# dual_vca_main.net
KiCad netlist of a schematic drawn in EAGLE
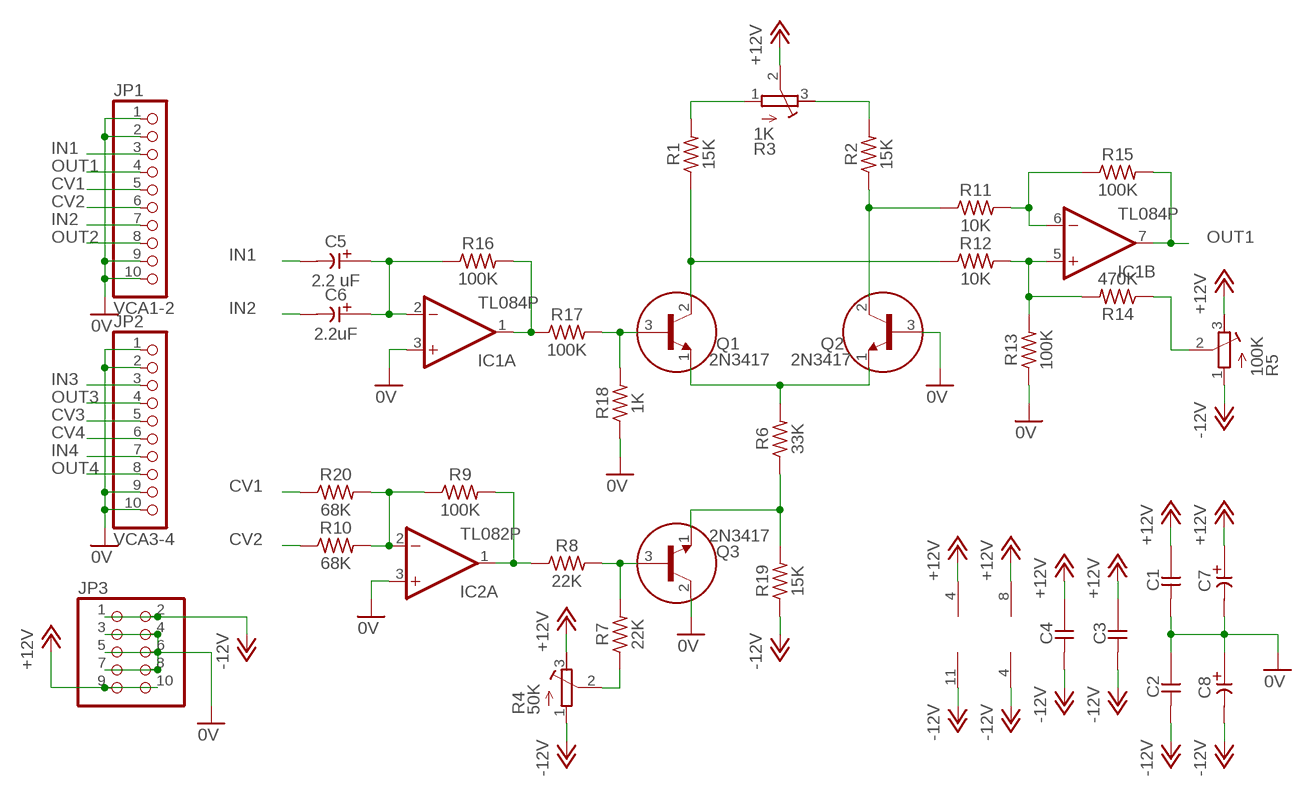
[diagram p0: schematic, sheet 1]

(export (version "E")
  (design (tool "Eeschema 10.0.6"))
  (components
    (comp (ref "C1")
      (value "CC-US025-024X044")
      (footprint "eagle-import:C025-024X044")
      (libsource (lib "eagle-import") (part "CC-US025-024X044"))
    )
    (comp (ref "C2")
      (value "CC-US025-024X044")
      (footprint "eagle-import:C025-024X044")
      (libsource (lib "eagle-import") (part "CC-US025-024X044"))
    )
    (comp (ref "C3")
      (value "CC-US025-024X044")
      (footprint "eagle-import:C025-024X044")
      (libsource (lib "eagle-import") (part "CC-US025-024X044"))
    )
    (comp (ref "C4")
      (value "CC-US025-024X044")
      (footprint "eagle-import:C025-024X044")
      (libsource (lib "eagle-import") (part "CC-US025-024X044"))
    )
    (comp (ref "C5")
      (value "2.2 uF")
      (footprint "eagle-import:E2-5")
      (libsource (lib "eagle-import") (part "CE-USE2-5"))
    )
    (comp (ref "C6")
      (value "2.2uF")
      (footprint "eagle-import:E2-5")
      (libsource (lib "eagle-import") (part "CE-USE2-5"))
    )
    (comp (ref "C7")
      (value "CE-USE2-5")
      (footprint "eagle-import:E2-5")
      (libsource (lib "eagle-import") (part "CE-USE2-5"))
    )
    (comp (ref "C8")
      (value "CE-USE2-5")
      (footprint "eagle-import:E2-5")
      (libsource (lib "eagle-import") (part "CE-USE2-5"))
    )
    (comp (ref "IC1")
      (value "TL084P")
      (footprint "eagle-import:DIL14")
      (libsource (lib "eagle-import") (part "TL084P"))
    )
    (comp (ref "IC2")
      (value "TL082P")
      (footprint "eagle-import:DIL08")
      (libsource (lib "eagle-import") (part "TL082P"))
    )
    (comp (ref "JP1")
      (value "VCA1-2")
      (footprint "eagle-import:1X10")
      (libsource (lib "eagle-import") (part "PINHD-1X10"))
    )
    (comp (ref "JP2")
      (value "VCA3-4")
      (footprint "eagle-import:1X10")
      (libsource (lib "eagle-import") (part "PINHD-1X10"))
    )
    (comp (ref "JP3")
      (value "PINHD-2X5")
      (footprint "eagle-import:2X05")
      (libsource (lib "eagle-import") (part "PINHD-2X5"))
    )
    (comp (ref "Q1")
      (value "2N3417")
      (footprint "eagle-import:TO92")
      (libsource (lib "eagle-import") (part "2N3417"))
    )
    (comp (ref "Q2")
      (value "2N3417")
      (footprint "eagle-import:TO92")
      (libsource (lib "eagle-import") (part "2N3417"))
    )
    (comp (ref "Q3")
      (value "2N3417")
      (footprint "eagle-import:TO92")
      (libsource (lib "eagle-import") (part "2N3417"))
    )
    (comp (ref "R1")
      (value "15K")
      (footprint "eagle-import:0207_7")
      (libsource (lib "eagle-import") (part "R"))
    )
    (comp (ref "R2")
      (value "15K")
      (footprint "eagle-import:0207_7")
      (libsource (lib "eagle-import") (part "R"))
    )
    (comp (ref "R3")
      (value "1K")
      (footprint "eagle-import:RTRIM3339P")
      (libsource (lib "eagle-import") (part "R-TRIMM3339P"))
    )
    (comp (ref "R4")
      (value "50K")
      (footprint "eagle-import:RTRIM3339P")
      (libsource (lib "eagle-import") (part "R-TRIMM3339P"))
    )
    (comp (ref "R5")
      (value "100K")
      (footprint "eagle-import:RTRIM3339P")
      (libsource (lib "eagle-import") (part "R-TRIMM3339P"))
    )
    (comp (ref "R6")
      (value "33K")
      (footprint "eagle-import:0207_7")
      (libsource (lib "eagle-import") (part "R"))
    )
    (comp (ref "R7")
      (value "22K")
      (footprint "eagle-import:0207_7")
      (libsource (lib "eagle-import") (part "R"))
    )
    (comp (ref "R8")
      (value "22K")
      (footprint "eagle-import:0207_7")
      (libsource (lib "eagle-import") (part "R"))
    )
    (comp (ref "R9")
      (value "100K")
      (footprint "eagle-import:0207_7")
      (libsource (lib "eagle-import") (part "R"))
    )
    (comp (ref "R10")
      (value "68K")
      (footprint "eagle-import:0207_7")
      (libsource (lib "eagle-import") (part "R"))
    )
    (comp (ref "R11")
      (value "10K")
      (footprint "eagle-import:0207_7")
      (libsource (lib "eagle-import") (part "R"))
    )
    (comp (ref "R12")
      (value "10K")
      (footprint "eagle-import:0207_7")
      (libsource (lib "eagle-import") (part "R"))
    )
    (comp (ref "R13")
      (value "100K")
      (footprint "eagle-import:0207_7")
      (libsource (lib "eagle-import") (part "R"))
    )
    (comp (ref "R14")
      (value "470K")
      (footprint "eagle-import:0207_7")
      (libsource (lib "eagle-import") (part "R"))
    )
    (comp (ref "R15")
      (value "100K")
      (footprint "eagle-import:0207_7")
      (libsource (lib "eagle-import") (part "R"))
    )
    (comp (ref "R16")
      (value "100K")
      (footprint "eagle-import:0207_7")
      (libsource (lib "eagle-import") (part "R"))
    )
    (comp (ref "R17")
      (value "100K")
      (footprint "eagle-import:0207_7")
      (libsource (lib "eagle-import") (part "R"))
    )
    (comp (ref "R18")
      (value "1K")
      (footprint "eagle-import:0207_7")
      (libsource (lib "eagle-import") (part "R"))
    )
    (comp (ref "R19")
      (value "15K")
      (footprint "eagle-import:0207_7")
      (libsource (lib "eagle-import") (part "R"))
    )
    (comp (ref "R20")
      (value "68K")
      (footprint "eagle-import:0207_7")
      (libsource (lib "eagle-import") (part "R"))
    )
  )
  (nets
    (net (code "1") (name "+12V") (class "Default")
      (node (ref "C1") (pin "1") (pinfunction "1_1") (pintype "passive"))
      (node (ref "C3") (pin "1") (pinfunction "1_1") (pintype "passive"))
      (node (ref "C4") (pin "1") (pinfunction "1_1") (pintype "passive"))
      (node (ref "C7") (pin "+") (pinfunction "+_+") (pintype "passive"))
      (node (ref "IC1") (pin "4") (pinfunction "V+_4") (pintype "power_in"))
      (node (ref "IC2") (pin "8") (pinfunction "V+_8") (pintype "power_in"))
      (node (ref "JP3") (pin "10") (pinfunction "10_10") (pintype "passive"))
      (node (ref "JP3") (pin "9") (pinfunction "9_9") (pintype "passive"))
      (node (ref "R3") (pin "2") (pinfunction "S_2") (pintype "passive"))
      (node (ref "R4") (pin "3") (pinfunction "E_3") (pintype "passive"))
      (node (ref "R5") (pin "3") (pinfunction "E_3") (pintype "passive"))
    )
    (net (code "2") (name "-12V") (class "Default")
      (node (ref "C2") (pin "2") (pinfunction "2_2") (pintype "passive"))
      (node (ref "C3") (pin "2") (pinfunction "2_2") (pintype "passive"))
      (node (ref "C4") (pin "2") (pinfunction "2_2") (pintype "passive"))
      (node (ref "C8") (pin "-") (pinfunction "-_-") (pintype "passive"))
      (node (ref "IC1") (pin "11") (pinfunction "V-_11") (pintype "power_in"))
      (node (ref "IC2") (pin "4") (pinfunction "V-_4") (pintype "power_in"))
      (node (ref "JP3") (pin "1") (pinfunction "1_1") (pintype "passive"))
      (node (ref "JP3") (pin "2") (pinfunction "2_2") (pintype "passive"))
      (node (ref "R19") (pin "1") (pinfunction "1_1") (pintype "passive"))
      (node (ref "R4") (pin "1") (pinfunction "A_1") (pintype "passive"))
      (node (ref "R5") (pin "1") (pinfunction "A_1") (pintype "passive"))
    )
    (net (code "3") (name "/CV1") (class "Default")
      (node (ref "JP1") (pin "5") (pinfunction "5_5") (pintype "passive"))
      (node (ref "R20") (pin "1") (pinfunction "1_1") (pintype "passive"))
    )
    (net (code "4") (name "/CV2") (class "Default")
      (node (ref "JP1") (pin "6") (pinfunction "6_6") (pintype "passive"))
      (node (ref "R10") (pin "1") (pinfunction "1_1") (pintype "passive"))
    )
    (net (code "5") (name "/CV3") (class "Default")
      (node (ref "JP2") (pin "5") (pinfunction "5_5") (pintype "passive"))
    )
    (net (code "6") (name "/CV4") (class "Default")
      (node (ref "JP2") (pin "6") (pinfunction "6_6") (pintype "passive"))
    )
    (net (code "7") (name "/IN1") (class "Default")
      (node (ref "C5") (pin "-") (pinfunction "-_-") (pintype "passive"))
      (node (ref "JP1") (pin "3") (pinfunction "3_3") (pintype "passive"))
    )
    (net (code "8") (name "/IN2") (class "Default")
      (node (ref "C6") (pin "-") (pinfunction "-_-") (pintype "passive"))
      (node (ref "JP1") (pin "7") (pinfunction "7_7") (pintype "passive"))
    )
    (net (code "9") (name "/IN3") (class "Default")
      (node (ref "JP2") (pin "3") (pinfunction "3_3") (pintype "passive"))
    )
    (net (code "10") (name "/IN4") (class "Default")
      (node (ref "JP2") (pin "7") (pinfunction "7_7") (pintype "passive"))
    )
    (net (code "11") (name "/OUT1") (class "Default")
      (node (ref "IC1") (pin "7") (pinfunction "OUT_7") (pintype "output"))
      (node (ref "JP1") (pin "4") (pinfunction "4_4") (pintype "passive"))
      (node (ref "R15") (pin "2") (pinfunction "2_2") (pintype "passive"))
    )
    (net (code "12") (name "/OUT2") (class "Default")
      (node (ref "JP1") (pin "8") (pinfunction "8_8") (pintype "passive"))
    )
    (net (code "13") (name "/OUT3") (class "Default")
      (node (ref "JP2") (pin "4") (pinfunction "4_4") (pintype "passive"))
    )
    (net (code "14") (name "/OUT4") (class "Default")
      (node (ref "JP2") (pin "8") (pinfunction "8_8") (pintype "passive"))
    )
    (net (code "15") (name "0V") (class "Default")
      (node (ref "C1") (pin "2") (pinfunction "2_2") (pintype "passive"))
      (node (ref "C2") (pin "1") (pinfunction "1_1") (pintype "passive"))
      (node (ref "C7") (pin "-") (pinfunction "-_-") (pintype "passive"))
      (node (ref "C8") (pin "+") (pinfunction "+_+") (pintype "passive"))
      (node (ref "IC1") (pin "3") (pinfunction "+IN_3") (pintype "input"))
      (node (ref "IC2") (pin "3") (pinfunction "+IN_3") (pintype "input"))
      (node (ref "JP1") (pin "1") (pinfunction "1_1") (pintype "passive"))
      (node (ref "JP1") (pin "10") (pinfunction "10_10") (pintype "passive"))
      (node (ref "JP1") (pin "2") (pinfunction "2_2") (pintype "passive"))
      (node (ref "JP1") (pin "9") (pinfunction "9_9") (pintype "passive"))
      (node (ref "JP2") (pin "1") (pinfunction "1_1") (pintype "passive"))
      (node (ref "JP2") (pin "10") (pinfunction "10_10") (pintype "passive"))
      (node (ref "JP2") (pin "2") (pinfunction "2_2") (pintype "passive"))
      (node (ref "JP2") (pin "9") (pinfunction "9_9") (pintype "passive"))
      (node (ref "JP3") (pin "3") (pinfunction "3_3") (pintype "passive"))
      (node (ref "JP3") (pin "4") (pinfunction "4_4") (pintype "passive"))
      (node (ref "JP3") (pin "5") (pinfunction "5_5") (pintype "passive"))
      (node (ref "JP3") (pin "6") (pinfunction "6_6") (pintype "passive"))
      (node (ref "JP3") (pin "7") (pinfunction "7_7") (pintype "passive"))
      (node (ref "JP3") (pin "8") (pinfunction "8_8") (pintype "passive"))
      (node (ref "Q2") (pin "3") (pinfunction "B_3") (pintype "passive"))
      (node (ref "Q3") (pin "2") (pinfunction "C_2") (pintype "passive"))
      (node (ref "R13") (pin "1") (pinfunction "1_1") (pintype "passive"))
      (node (ref "R18") (pin "1") (pinfunction "1_1") (pintype "passive"))
    )
    (net (code "16") (name "Net-(IC1A--IN)") (class "Default")
      (node (ref "C5") (pin "+") (pinfunction "+_+") (pintype "passive"))
      (node (ref "C6") (pin "+") (pinfunction "+_+") (pintype "passive"))
      (node (ref "IC1") (pin "2") (pinfunction "-IN_2") (pintype "input"))
      (node (ref "R16") (pin "1") (pinfunction "1_1") (pintype "passive"))
    )
    (net (code "17") (name "Net-(IC1A-OUT)") (class "Default")
      (node (ref "IC1") (pin "1") (pinfunction "OUT_1") (pintype "output"))
      (node (ref "R16") (pin "2") (pinfunction "2_2") (pintype "passive"))
      (node (ref "R17") (pin "1") (pinfunction "1_1") (pintype "passive"))
    )
    (net (code "18") (name "Net-(IC1B-+IN)") (class "Default")
      (node (ref "IC1") (pin "5") (pinfunction "+IN_5") (pintype "input"))
      (node (ref "R12") (pin "2") (pinfunction "2_2") (pintype "passive"))
      (node (ref "R13") (pin "2") (pinfunction "2_2") (pintype "passive"))
      (node (ref "R14") (pin "2") (pinfunction "2_2") (pintype "passive"))
    )
    (net (code "19") (name "Net-(IC1B--IN)") (class "Default")
      (node (ref "IC1") (pin "6") (pinfunction "-IN_6") (pintype "input"))
      (node (ref "R11") (pin "2") (pinfunction "2_2") (pintype "passive"))
      (node (ref "R15") (pin "1") (pinfunction "1_1") (pintype "passive"))
    )
    (net (code "20") (name "Net-(IC2A--IN)") (class "Default")
      (node (ref "IC2") (pin "2") (pinfunction "-IN_2") (pintype "input"))
      (node (ref "R10") (pin "2") (pinfunction "2_2") (pintype "passive"))
      (node (ref "R20") (pin "2") (pinfunction "2_2") (pintype "passive"))
      (node (ref "R9") (pin "1") (pinfunction "1_1") (pintype "passive"))
    )
    (net (code "21") (name "Net-(IC2A-OUT)") (class "Default")
      (node (ref "IC2") (pin "1") (pinfunction "OUT_1") (pintype "output"))
      (node (ref "R8") (pin "1") (pinfunction "1_1") (pintype "passive"))
      (node (ref "R9") (pin "2") (pinfunction "2_2") (pintype "passive"))
    )
    (net (code "22") (name "Net-(Q1-B)") (class "Default")
      (node (ref "Q1") (pin "3") (pinfunction "B_3") (pintype "passive"))
      (node (ref "R17") (pin "2") (pinfunction "2_2") (pintype "passive"))
      (node (ref "R18") (pin "2") (pinfunction "2_2") (pintype "passive"))
    )
    (net (code "23") (name "Net-(Q1-C)") (class "Default")
      (node (ref "Q1") (pin "2") (pinfunction "C_2") (pintype "passive"))
      (node (ref "R1") (pin "1") (pinfunction "1_1") (pintype "passive"))
      (node (ref "R12") (pin "1") (pinfunction "1_1") (pintype "passive"))
    )
    (net (code "24") (name "Net-(Q1-E)") (class "Default")
      (node (ref "Q1") (pin "1") (pinfunction "E_1") (pintype "passive"))
      (node (ref "Q2") (pin "1") (pinfunction "E_1") (pintype "passive"))
      (node (ref "R6") (pin "2") (pinfunction "2_2") (pintype "passive"))
    )
    (net (code "25") (name "Net-(Q2-C)") (class "Default")
      (node (ref "Q2") (pin "2") (pinfunction "C_2") (pintype "passive"))
      (node (ref "R11") (pin "1") (pinfunction "1_1") (pintype "passive"))
      (node (ref "R2") (pin "1") (pinfunction "1_1") (pintype "passive"))
    )
    (net (code "26") (name "Net-(Q3-B)") (class "Default")
      (node (ref "Q3") (pin "3") (pinfunction "B_3") (pintype "passive"))
      (node (ref "R7") (pin "2") (pinfunction "2_2") (pintype "passive"))
      (node (ref "R8") (pin "2") (pinfunction "2_2") (pintype "passive"))
    )
    (net (code "27") (name "Net-(Q3-E)") (class "Default")
      (node (ref "Q3") (pin "1") (pinfunction "E_1") (pintype "passive"))
      (node (ref "R19") (pin "2") (pinfunction "2_2") (pintype "passive"))
      (node (ref "R6") (pin "1") (pinfunction "1_1") (pintype "passive"))
    )
    (net (code "28") (name "Net-(R3-A)") (class "Default")
      (node (ref "R1") (pin "2") (pinfunction "2_2") (pintype "passive"))
      (node (ref "R3") (pin "1") (pinfunction "A_1") (pintype "passive"))
    )
    (net (code "29") (name "Net-(R3-E)") (class "Default")
      (node (ref "R2") (pin "2") (pinfunction "2_2") (pintype "passive"))
      (node (ref "R3") (pin "3") (pinfunction "E_3") (pintype "passive"))
    )
    (net (code "30") (name "Net-(R4-S)") (class "Default")
      (node (ref "R4") (pin "2") (pinfunction "S_2") (pintype "passive"))
      (node (ref "R7") (pin "1") (pinfunction "1_1") (pintype "passive"))
    )
    (net (code "31") (name "Net-(R5-S)") (class "Default")
      (node (ref "R14") (pin "1") (pinfunction "1_1") (pintype "passive"))
      (node (ref "R5") (pin "2") (pinfunction "S_2") (pintype "passive"))
    )
  )
)
